# programmer-shield.net
KiCad netlist of a schematic drawn in Altium Designer
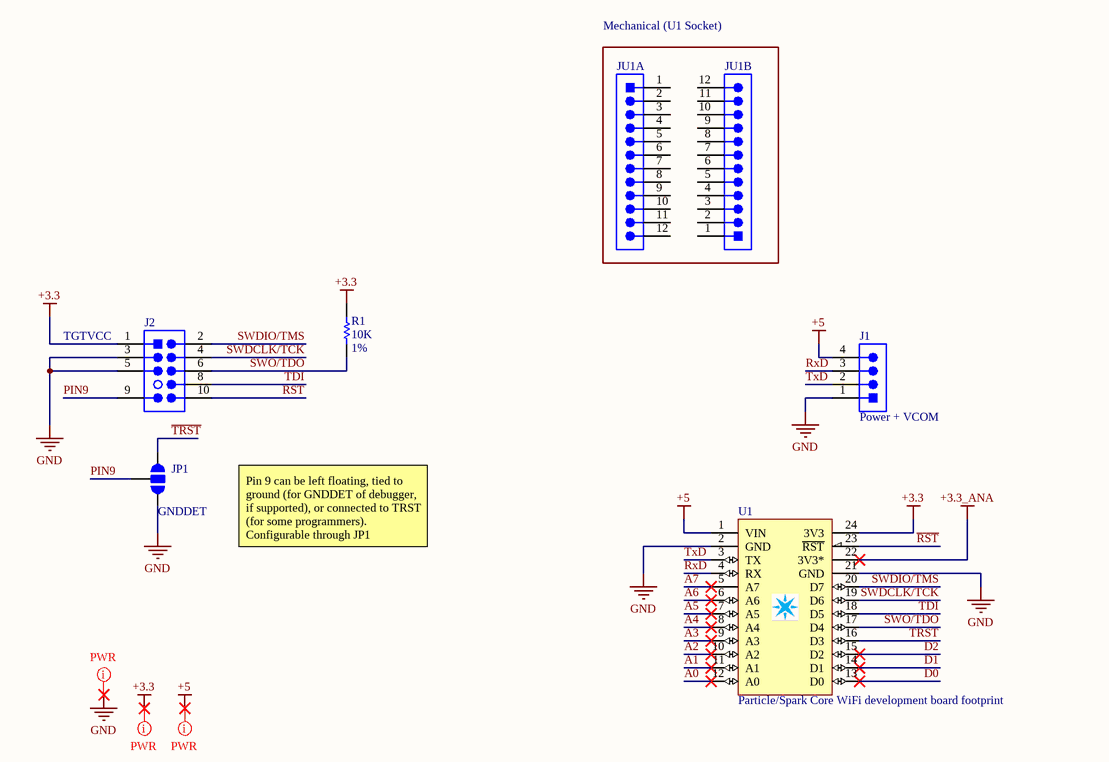
[diagram p0: programmer-shield.SchDoc]

(export (version "E")
  (design (tool "Eeschema 10.0.6"))
  (components
    (comp (ref "J1")
      (value "4 contacts Male header")
      (footprint "70553-0003")
      (description "Connector Male Header 1X4 horizontal 4contacts 0.100in pitch Gold finish shrouded")
      (fields (field (name "MANUFACTURER") "Molex"))
      (libsource (lib "Connectors") (part "Header 1X4"))
    )
    (comp (ref "J2")
      (value "Cortex Debug, 0.050\" 10 Pin")
      (footprint "FTSH-105-01-F-DV-007-K PLUGIN")
      (description "10 Pin Shrouded Header, 0.050\", Key Pin 7")
      (fields (field (name "MANUFACTURER") "Samtech"))
      (libsource (lib "Connectors") (part "Cortex Debug"))
    )
    (comp (ref "JP1")
      (value "SMD JMP 3 Pad")
      (footprint "SMT-JUMPER_3_NO_SILK")
      (libsource (lib "Hardware") (part "JMP_SMT_3_NO"))
    )
    (comp (ref "JU1A")
      (value "12 contacts Female header")
      (footprint "SSW-112-01-G-S")
      (description "Connector Female Header 1X12 vertical 12 contacts  pitch Gold finish")
      (fields (field (name "MANUFACTURER") "SamTec"))
      (libsource (lib "Connectors") (part "Header 1X12"))
    )
    (comp (ref "JU1B")
      (value "12 contacts Female header")
      (footprint "SSW-112-01-G-S")
      (description "Connector Female Header 1X12 vertical 12 contacts  pitch Gold finish")
      (fields (field (name "MANUFACTURER") "SamTec"))
      (libsource (lib "") (part "Header 1X12_1"))
    )
    (comp (ref "R1")
      (value "RES 0603 10K 1%")
      (footprint "0603_RES")
      (description "Resistor Surface Mount, 10K Ohms, 0603 Footprint, 1% Tolerance 0.1W")
      (fields
        (field (name "VAL") "10K")
        (field (name "TOL") "1%")
        (field (name "MANUFACTURER") "Various")
        (field (name "TOLERANCE") "1%")
      )
      (libsource (lib "Passive Components") (part "res"))
    )
    (comp (ref "U1")
      (value "Particle/Spark Core WiFi development board footprint")
      (footprint "SPARK_CORE_STACKING_SOCKET")
      (libsource (lib "Particle-Devices") (part "SPARK_CORE"))
    )
  )
  (nets
    (net (code "1") (name "+3.3") (class "Default")
      (node (ref "J2") (pin "1") (pinfunction "VCC_1") (pintype "power_in"))
      (node (ref "R1") (pin "2") (pinfunction "2_2") (pintype "passive"))
      (node (ref "U1") (pin "24") (pinfunction "3V3_24") (pintype "power_in"))
    )
    (net (code "2") (name "+3.3_ANA") (class "Default")
      (node (ref "U1") (pin "22") (pinfunction "3V3*_22") (pintype "power_in"))
    )
    (net (code "3") (name "+5") (class "Default")
      (node (ref "J1") (pin "4") (pinfunction "4_4") (pintype "passive"))
      (node (ref "U1") (pin "1") (pinfunction "VIN_1") (pintype "power_in"))
    )
    (net (code "4") (name "/A0") (class "Default")
      (node (ref "U1") (pin "12") (pinfunction "A0_12") (pintype "bidirectional+no_connect"))
    )
    (net (code "5") (name "/A1") (class "Default")
      (node (ref "U1") (pin "11") (pinfunction "A1_11") (pintype "bidirectional+no_connect"))
    )
    (net (code "6") (name "/A2") (class "Default")
      (node (ref "U1") (pin "10") (pinfunction "A2_10") (pintype "bidirectional+no_connect"))
    )
    (net (code "7") (name "/A3") (class "Default")
      (node (ref "U1") (pin "9") (pinfunction "A3_9") (pintype "bidirectional+no_connect"))
    )
    (net (code "8") (name "/A4") (class "Default")
      (node (ref "U1") (pin "8") (pinfunction "A4_8") (pintype "bidirectional+no_connect"))
    )
    (net (code "9") (name "/A5") (class "Default")
      (node (ref "U1") (pin "7") (pinfunction "A5_7") (pintype "bidirectional+no_connect"))
    )
    (net (code "10") (name "/A6") (class "Default")
      (node (ref "U1") (pin "6") (pinfunction "A6_6") (pintype "bidirectional+no_connect"))
    )
    (net (code "11") (name "/A7") (class "Default")
      (node (ref "U1") (pin "5") (pinfunction "A7_5") (pintype "passive+no_connect"))
    )
    (net (code "12") (name "/D0") (class "Default")
      (node (ref "U1") (pin "13") (pinfunction "D0_13") (pintype "bidirectional+no_connect"))
    )
    (net (code "13") (name "/D1") (class "Default")
      (node (ref "U1") (pin "14") (pinfunction "D1_14") (pintype "bidirectional+no_connect"))
    )
    (net (code "14") (name "/D2") (class "Default")
      (node (ref "U1") (pin "15") (pinfunction "D2_15") (pintype "bidirectional+no_connect"))
    )
    (net (code "15") (name "/PIN9") (class "Default")
      (node (ref "J2") (pin "9") (pinfunction "GNDDetect_9") (pintype "power_in"))
      (node (ref "JP1") (pin "2") (pinfunction "2_2") (pintype "passive"))
    )
    (net (code "16") (name "/RST") (class "Default")
      (node (ref "J2") (pin "10") (pinfunction "RESET_10") (pintype "passive"))
      (node (ref "U1") (pin "23") (pinfunction "RST_23") (pintype "passive"))
    )
    (net (code "17") (name "/RxD") (class "Default")
      (node (ref "J1") (pin "3") (pinfunction "3_3") (pintype "passive"))
      (node (ref "U1") (pin "4") (pinfunction "RX_4") (pintype "bidirectional"))
    )
    (net (code "18") (name "/SWDCLK{slash}TCK") (class "Default")
      (node (ref "J2") (pin "4") (pinfunction "SWDCLK/TCK_4") (pintype "passive"))
      (node (ref "U1") (pin "19") (pinfunction "D6_19") (pintype "bidirectional"))
    )
    (net (code "19") (name "/SWDIO{slash}TMS") (class "Default")
      (node (ref "J2") (pin "2") (pinfunction "SWDIO/TMS_2") (pintype "passive"))
      (node (ref "U1") (pin "20") (pinfunction "D7_20") (pintype "bidirectional"))
    )
    (net (code "20") (name "/SWO{slash}TDO") (class "Default")
      (node (ref "J2") (pin "6") (pinfunction "SWO/TDO_6") (pintype "passive"))
      (node (ref "R1") (pin "1") (pinfunction "1_1") (pintype "passive"))
      (node (ref "U1") (pin "17") (pinfunction "D4_17") (pintype "bidirectional"))
    )
    (net (code "21") (name "/TDI") (class "Default")
      (node (ref "J2") (pin "8") (pinfunction "NC/TDI_8") (pintype "passive"))
      (node (ref "U1") (pin "18") (pinfunction "D5_18") (pintype "bidirectional"))
    )
    (net (code "22") (name "/TRST") (class "Default")
      (node (ref "JP1") (pin "1") (pinfunction "1_1") (pintype "passive"))
      (node (ref "U1") (pin "16") (pinfunction "D3_16") (pintype "bidirectional"))
    )
    (net (code "23") (name "/TxD") (class "Default")
      (node (ref "J1") (pin "2") (pinfunction "2_2") (pintype "passive"))
      (node (ref "U1") (pin "3") (pinfunction "TX_3") (pintype "bidirectional"))
    )
    (net (code "24") (name "GND") (class "Default")
      (node (ref "J1") (pin "1") (pinfunction "1_1") (pintype "passive"))
      (node (ref "J2") (pin "3") (pinfunction "GND_3") (pintype "power_in"))
      (node (ref "J2") (pin "5") (pinfunction "GND_5") (pintype "power_in"))
      (node (ref "JP1") (pin "3") (pinfunction "3_3") (pintype "passive"))
      (node (ref "U1") (pin "2") (pinfunction "GND_2") (pintype "power_in"))
      (node (ref "U1") (pin "21") (pinfunction "GND_21") (pintype "power_in"))
    )
    (net (code "25") (name "unconnected-(JU1A-Pad1)") (class "Default")
      (node (ref "JU1A") (pin "1") (pinfunction "1_1") (pintype "passive"))
    )
    (net (code "26") (name "unconnected-(JU1A-Pad2)") (class "Default")
      (node (ref "JU1A") (pin "2") (pinfunction "2_2") (pintype "passive"))
    )
    (net (code "27") (name "unconnected-(JU1A-Pad3)") (class "Default")
      (node (ref "JU1A") (pin "3") (pinfunction "3_3") (pintype "passive"))
    )
    (net (code "28") (name "unconnected-(JU1A-Pad4)") (class "Default")
      (node (ref "JU1A") (pin "4") (pinfunction "4_4") (pintype "passive"))
    )
    (net (code "29") (name "unconnected-(JU1A-Pad5)") (class "Default")
      (node (ref "JU1A") (pin "5") (pinfunction "5_5") (pintype "passive"))
    )
    (net (code "30") (name "unconnected-(JU1A-Pad6)") (class "Default")
      (node (ref "JU1A") (pin "6") (pinfunction "6_6") (pintype "passive"))
    )
    (net (code "31") (name "unconnected-(JU1A-Pad7)") (class "Default")
      (node (ref "JU1A") (pin "7") (pinfunction "7_7") (pintype "passive"))
    )
    (net (code "32") (name "unconnected-(JU1A-Pad8)") (class "Default")
      (node (ref "JU1A") (pin "8") (pinfunction "8_8") (pintype "passive"))
    )
    (net (code "33") (name "unconnected-(JU1A-Pad9)") (class "Default")
      (node (ref "JU1A") (pin "9") (pinfunction "9_9") (pintype "passive"))
    )
    (net (code "34") (name "unconnected-(JU1A-Pad10)") (class "Default")
      (node (ref "JU1A") (pin "10") (pinfunction "10_10") (pintype "passive"))
    )
    (net (code "35") (name "unconnected-(JU1A-Pad11)") (class "Default")
      (node (ref "JU1A") (pin "11") (pinfunction "11_11") (pintype "passive"))
    )
    (net (code "36") (name "unconnected-(JU1A-Pad12)") (class "Default")
      (node (ref "JU1A") (pin "12") (pinfunction "12_12") (pintype "passive"))
    )
    (net (code "37") (name "unconnected-(JU1B-Pad1)") (class "Default")
      (node (ref "JU1B") (pin "1") (pinfunction "1_1") (pintype "passive"))
    )
    (net (code "38") (name "unconnected-(JU1B-Pad2)") (class "Default")
      (node (ref "JU1B") (pin "2") (pinfunction "2_2") (pintype "passive"))
    )
    (net (code "39") (name "unconnected-(JU1B-Pad3)") (class "Default")
      (node (ref "JU1B") (pin "3") (pinfunction "3_3") (pintype "passive"))
    )
    (net (code "40") (name "unconnected-(JU1B-Pad4)") (class "Default")
      (node (ref "JU1B") (pin "4") (pinfunction "4_4") (pintype "passive"))
    )
    (net (code "41") (name "unconnected-(JU1B-Pad5)") (class "Default")
      (node (ref "JU1B") (pin "5") (pinfunction "5_5") (pintype "passive"))
    )
    (net (code "42") (name "unconnected-(JU1B-Pad6)") (class "Default")
      (node (ref "JU1B") (pin "6") (pinfunction "6_6") (pintype "passive"))
    )
    (net (code "43") (name "unconnected-(JU1B-Pad7)") (class "Default")
      (node (ref "JU1B") (pin "7") (pinfunction "7_7") (pintype "passive"))
    )
    (net (code "44") (name "unconnected-(JU1B-Pad8)") (class "Default")
      (node (ref "JU1B") (pin "8") (pinfunction "8_8") (pintype "passive"))
    )
    (net (code "45") (name "unconnected-(JU1B-Pad9)") (class "Default")
      (node (ref "JU1B") (pin "9") (pinfunction "9_9") (pintype "passive"))
    )
    (net (code "46") (name "unconnected-(JU1B-Pad10)") (class "Default")
      (node (ref "JU1B") (pin "10") (pinfunction "10_10") (pintype "passive"))
    )
    (net (code "47") (name "unconnected-(JU1B-Pad11)") (class "Default")
      (node (ref "JU1B") (pin "11") (pinfunction "11_11") (pintype "passive"))
    )
    (net (code "48") (name "unconnected-(JU1B-Pad12)") (class "Default")
      (node (ref "JU1B") (pin "12") (pinfunction "12_12") (pintype "passive"))
    )
  )
)
